# dice.net
KiCad netlist of a schematic drawn in EAGLE
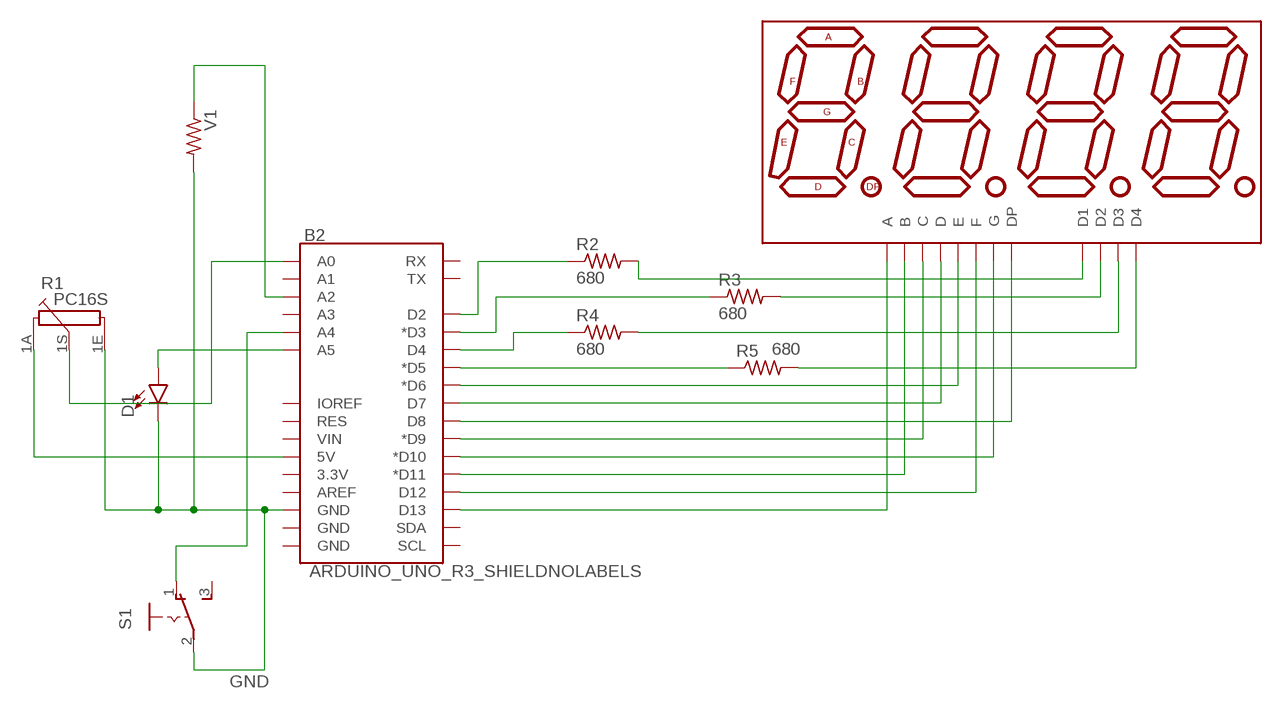
[diagram p0: schematic, sheet 1]

(export (version "E")
  (design (tool "Eeschema 10.0.6"))
  (components
    (comp (ref "B2")
      (value "ARDUINO_UNO_R3_SHIELDNOLABELS")
      (footprint "eagle-import:UNO_R3_SHIELD_NOLABELS")
      (libsource (lib "eagle-import") (part "ARDUINO_UNO_R3_SHIELDNOLABELS"))
    )
    (comp (ref "D1")
      (value "LED5MM")
      (footprint "eagle-import:LED_5MM")
      (libsource (lib "eagle-import") (part "LED5MM"))
    )
    (comp (ref "DISP1")
      (value "ATA8041AB")
      (footprint "eagle-import:7-SEGMENT-4DIGIT-20MM")
      (libsource (lib "eagle-import") (part "7-SEGMENT-4DIGIT-20MM-BLUE"))
    )
    (comp (ref "R1")
      (value "PC16S")
      (footprint "eagle-import:PC16S")
      (libsource (lib "eagle-import") (part "PC16S"))
    )
    (comp (ref "R2")
      (value "680")
      (footprint "eagle-import:0204_7")
      (libsource (lib "eagle-import") (part "R-US_0204/7"))
    )
    (comp (ref "R3")
      (value "680")
      (footprint "eagle-import:0204_7")
      (libsource (lib "eagle-import") (part "R-US_0204/7"))
    )
    (comp (ref "R4")
      (value "680")
      (footprint "eagle-import:0204_7")
      (libsource (lib "eagle-import") (part "R-US_0204/7"))
    )
    (comp (ref "R5")
      (value "680")
      (footprint "eagle-import:0204_7")
      (libsource (lib "eagle-import") (part "R-US_0204/7"))
    )
    (comp (ref "S1")
      (value "255SB")
      (footprint "eagle-import:255SB")
      (libsource (lib "eagle-import") (part "255SB"))
    )
    (comp (ref "V1")
      (value "R-US_0414/15")
      (footprint "eagle-import:0414_15")
      (libsource (lib "eagle-import") (part "R-US_0414/15"))
    )
  )
  (nets
    (net (code "1") (name "/GND") (class "Default")
      (node (ref "B2") (pin "GND@2") (pinfunction "GND_GND@2") (pintype "bidirectional"))
      (node (ref "D1") (pin "K") (pinfunction "C_K") (pintype "passive"))
      (node (ref "R1") (pin "1E") (pinfunction "1E_1E") (pintype "passive"))
      (node (ref "S1") (pin "2") (pinfunction "P_2") (pintype "passive"))
      (node (ref "V1") (pin "2") (pinfunction "2_2") (pintype "passive"))
    )
    (net (code "2") (name "Net-(B2-*D3)") (class "Default")
      (node (ref "B2") (pin "D3") (pinfunction "*D3_D3") (pintype "bidirectional"))
      (node (ref "R3") (pin "1") (pinfunction "1_1") (pintype "passive"))
    )
    (net (code "3") (name "Net-(B2-*D5)") (class "Default")
      (node (ref "B2") (pin "D5") (pinfunction "*D5_D5") (pintype "bidirectional"))
      (node (ref "R5") (pin "1") (pinfunction "1_1") (pintype "passive"))
    )
    (net (code "4") (name "Net-(B2-*D6)") (class "Default")
      (node (ref "B2") (pin "D6") (pinfunction "*D6_D6") (pintype "bidirectional"))
      (node (ref "DISP1") (pin "1") (pinfunction "E_1") (pintype "bidirectional"))
    )
    (net (code "5") (name "Net-(B2-*D9)") (class "Default")
      (node (ref "B2") (pin "D9") (pinfunction "*D9_D9") (pintype "bidirectional"))
      (node (ref "DISP1") (pin "4") (pinfunction "C_4") (pintype "bidirectional"))
    )
    (net (code "6") (name "Net-(B2-*D10)") (class "Default")
      (node (ref "B2") (pin "D10") (pinfunction "*D10_D10") (pintype "bidirectional"))
      (node (ref "DISP1") (pin "5") (pinfunction "G_5") (pintype "bidirectional"))
    )
    (net (code "7") (name "Net-(B2-*D11)") (class "Default")
      (node (ref "B2") (pin "D11") (pinfunction "*D11_D11") (pintype "bidirectional"))
      (node (ref "DISP1") (pin "7") (pinfunction "B_7") (pintype "bidirectional"))
    )
    (net (code "8") (name "Net-(B2-Pad5V)") (class "Default")
      (node (ref "B2") (pin "5V") (pinfunction "5V_5V") (pintype "bidirectional"))
      (node (ref "R1") (pin "1A") (pinfunction "1A_1A") (pintype "passive"))
    )
    (net (code "9") (name "Net-(B2-PadA0)") (class "Default")
      (node (ref "B2") (pin "A0") (pinfunction "A0_A0") (pintype "bidirectional"))
      (node (ref "R1") (pin "1S") (pinfunction "1S_1S") (pintype "passive"))
    )
    (net (code "10") (name "Net-(B2-PadA2)") (class "Default")
      (node (ref "B2") (pin "A2") (pinfunction "A2_A2") (pintype "bidirectional"))
      (node (ref "V1") (pin "1") (pinfunction "1_1") (pintype "passive"))
    )
    (net (code "11") (name "Net-(B2-PadA5)") (class "Default")
      (node (ref "B2") (pin "A5") (pinfunction "A5_A5") (pintype "bidirectional"))
      (node (ref "D1") (pin "A") (pinfunction "A_A") (pintype "passive"))
    )
    (net (code "12") (name "Net-(B2-PadD2)") (class "Default")
      (node (ref "B2") (pin "D2") (pinfunction "D2_D2") (pintype "bidirectional"))
      (node (ref "R2") (pin "1") (pinfunction "1_1") (pintype "passive"))
    )
    (net (code "13") (name "Net-(B2-PadD4)") (class "Default")
      (node (ref "B2") (pin "D4") (pinfunction "D4_D4") (pintype "bidirectional"))
      (node (ref "R4") (pin "1") (pinfunction "1_1") (pintype "passive"))
    )
    (net (code "14") (name "Net-(DISP1-A)") (class "Default")
      (node (ref "B2") (pin "D13") (pinfunction "D13_D13") (pintype "bidirectional"))
      (node (ref "DISP1") (pin "11") (pinfunction "A_11") (pintype "bidirectional"))
    )
    (net (code "15") (name "Net-(DISP1-D)") (class "Default")
      (node (ref "B2") (pin "D7") (pinfunction "D7_D7") (pintype "bidirectional"))
      (node (ref "DISP1") (pin "2") (pinfunction "D_2") (pintype "bidirectional"))
    )
    (net (code "16") (name "Net-(DISP1-D1)") (class "Default")
      (node (ref "DISP1") (pin "12") (pinfunction "D1_12") (pintype "bidirectional"))
      (node (ref "R2") (pin "2") (pinfunction "2_2") (pintype "passive"))
    )
    (net (code "17") (name "Net-(DISP1-D2)") (class "Default")
      (node (ref "DISP1") (pin "9") (pinfunction "D2_9") (pintype "bidirectional"))
      (node (ref "R3") (pin "2") (pinfunction "2_2") (pintype "passive"))
    )
    (net (code "18") (name "Net-(DISP1-D3)") (class "Default")
      (node (ref "DISP1") (pin "8") (pinfunction "D3_8") (pintype "bidirectional"))
      (node (ref "R4") (pin "2") (pinfunction "2_2") (pintype "passive"))
    )
    (net (code "19") (name "Net-(DISP1-D4)") (class "Default")
      (node (ref "DISP1") (pin "6") (pinfunction "D4_6") (pintype "bidirectional"))
      (node (ref "R5") (pin "2") (pinfunction "2_2") (pintype "passive"))
    )
    (net (code "20") (name "Net-(DISP1-DP)") (class "Default")
      (node (ref "B2") (pin "D8") (pinfunction "D8_D8") (pintype "bidirectional"))
      (node (ref "DISP1") (pin "3") (pinfunction "DP_3") (pintype "bidirectional"))
    )
    (net (code "21") (name "Net-(DISP1-F)") (class "Default")
      (node (ref "B2") (pin "D12") (pinfunction "D12_D12") (pintype "bidirectional"))
      (node (ref "DISP1") (pin "10") (pinfunction "F_10") (pintype "bidirectional"))
    )
    (net (code "22") (name "Net-(S1-O)") (class "Default")
      (node (ref "B2") (pin "A4") (pinfunction "A4_A4") (pintype "bidirectional"))
      (node (ref "S1") (pin "1") (pinfunction "O_1") (pintype "passive"))
    )
    (net (code "23") (name "unconnected-(B2-GND-PadGND@0)") (class "Default")
      (node (ref "B2") (pin "GND@0") (pinfunction "GND_GND@0") (pintype "bidirectional"))
    )
    (net (code "24") (name "unconnected-(B2-GND-PadGND@1)") (class "Default")
      (node (ref "B2") (pin "GND@1") (pinfunction "GND_GND@1") (pintype "bidirectional"))
    )
    (net (code "25") (name "unconnected-(B2-Pad3.3V)") (class "Default")
      (node (ref "B2") (pin "3.3V") (pinfunction "3.3V_3.3V") (pintype "bidirectional"))
    )
    (net (code "26") (name "unconnected-(B2-PadA1)") (class "Default")
      (node (ref "B2") (pin "A1") (pinfunction "A1_A1") (pintype "bidirectional"))
    )
    (net (code "27") (name "unconnected-(B2-PadA3)") (class "Default")
      (node (ref "B2") (pin "A3") (pinfunction "A3_A3") (pintype "bidirectional"))
    )
    (net (code "28") (name "unconnected-(B2-PadAREF)") (class "Default")
      (node (ref "B2") (pin "AREF") (pinfunction "AREF_AREF") (pintype "bidirectional"))
    )
    (net (code "29") (name "unconnected-(B2-PadIOREF)") (class "Default")
      (node (ref "B2") (pin "IOREF") (pinfunction "IOREF_IOREF") (pintype "bidirectional"))
    )
    (net (code "30") (name "unconnected-(B2-PadRES)") (class "Default")
      (node (ref "B2") (pin "RES") (pinfunction "RES_RES") (pintype "bidirectional"))
    )
    (net (code "31") (name "unconnected-(B2-PadRX)") (class "Default")
      (node (ref "B2") (pin "RX") (pinfunction "RX_RX") (pintype "bidirectional"))
    )
    (net (code "32") (name "unconnected-(B2-PadSCL)") (class "Default")
      (node (ref "B2") (pin "SCL") (pinfunction "SCL_SCL") (pintype "bidirectional"))
    )
    (net (code "33") (name "unconnected-(B2-PadSDA)") (class "Default")
      (node (ref "B2") (pin "SDA") (pinfunction "SDA_SDA") (pintype "bidirectional"))
    )
    (net (code "34") (name "unconnected-(B2-PadTX)") (class "Default")
      (node (ref "B2") (pin "TX") (pinfunction "TX_TX") (pintype "bidirectional"))
    )
    (net (code "35") (name "unconnected-(B2-PadVIN)") (class "Default")
      (node (ref "B2") (pin "VIN") (pinfunction "VIN_VIN") (pintype "bidirectional"))
    )
    (net (code "36") (name "unconnected-(S1-S-Pad3)") (class "Default")
      (node (ref "S1") (pin "3") (pinfunction "S_3") (pintype "passive"))
    )
  )
)
